# esp32-Prototipo.net
KiCad netlist of a schematic drawn in EAGLE
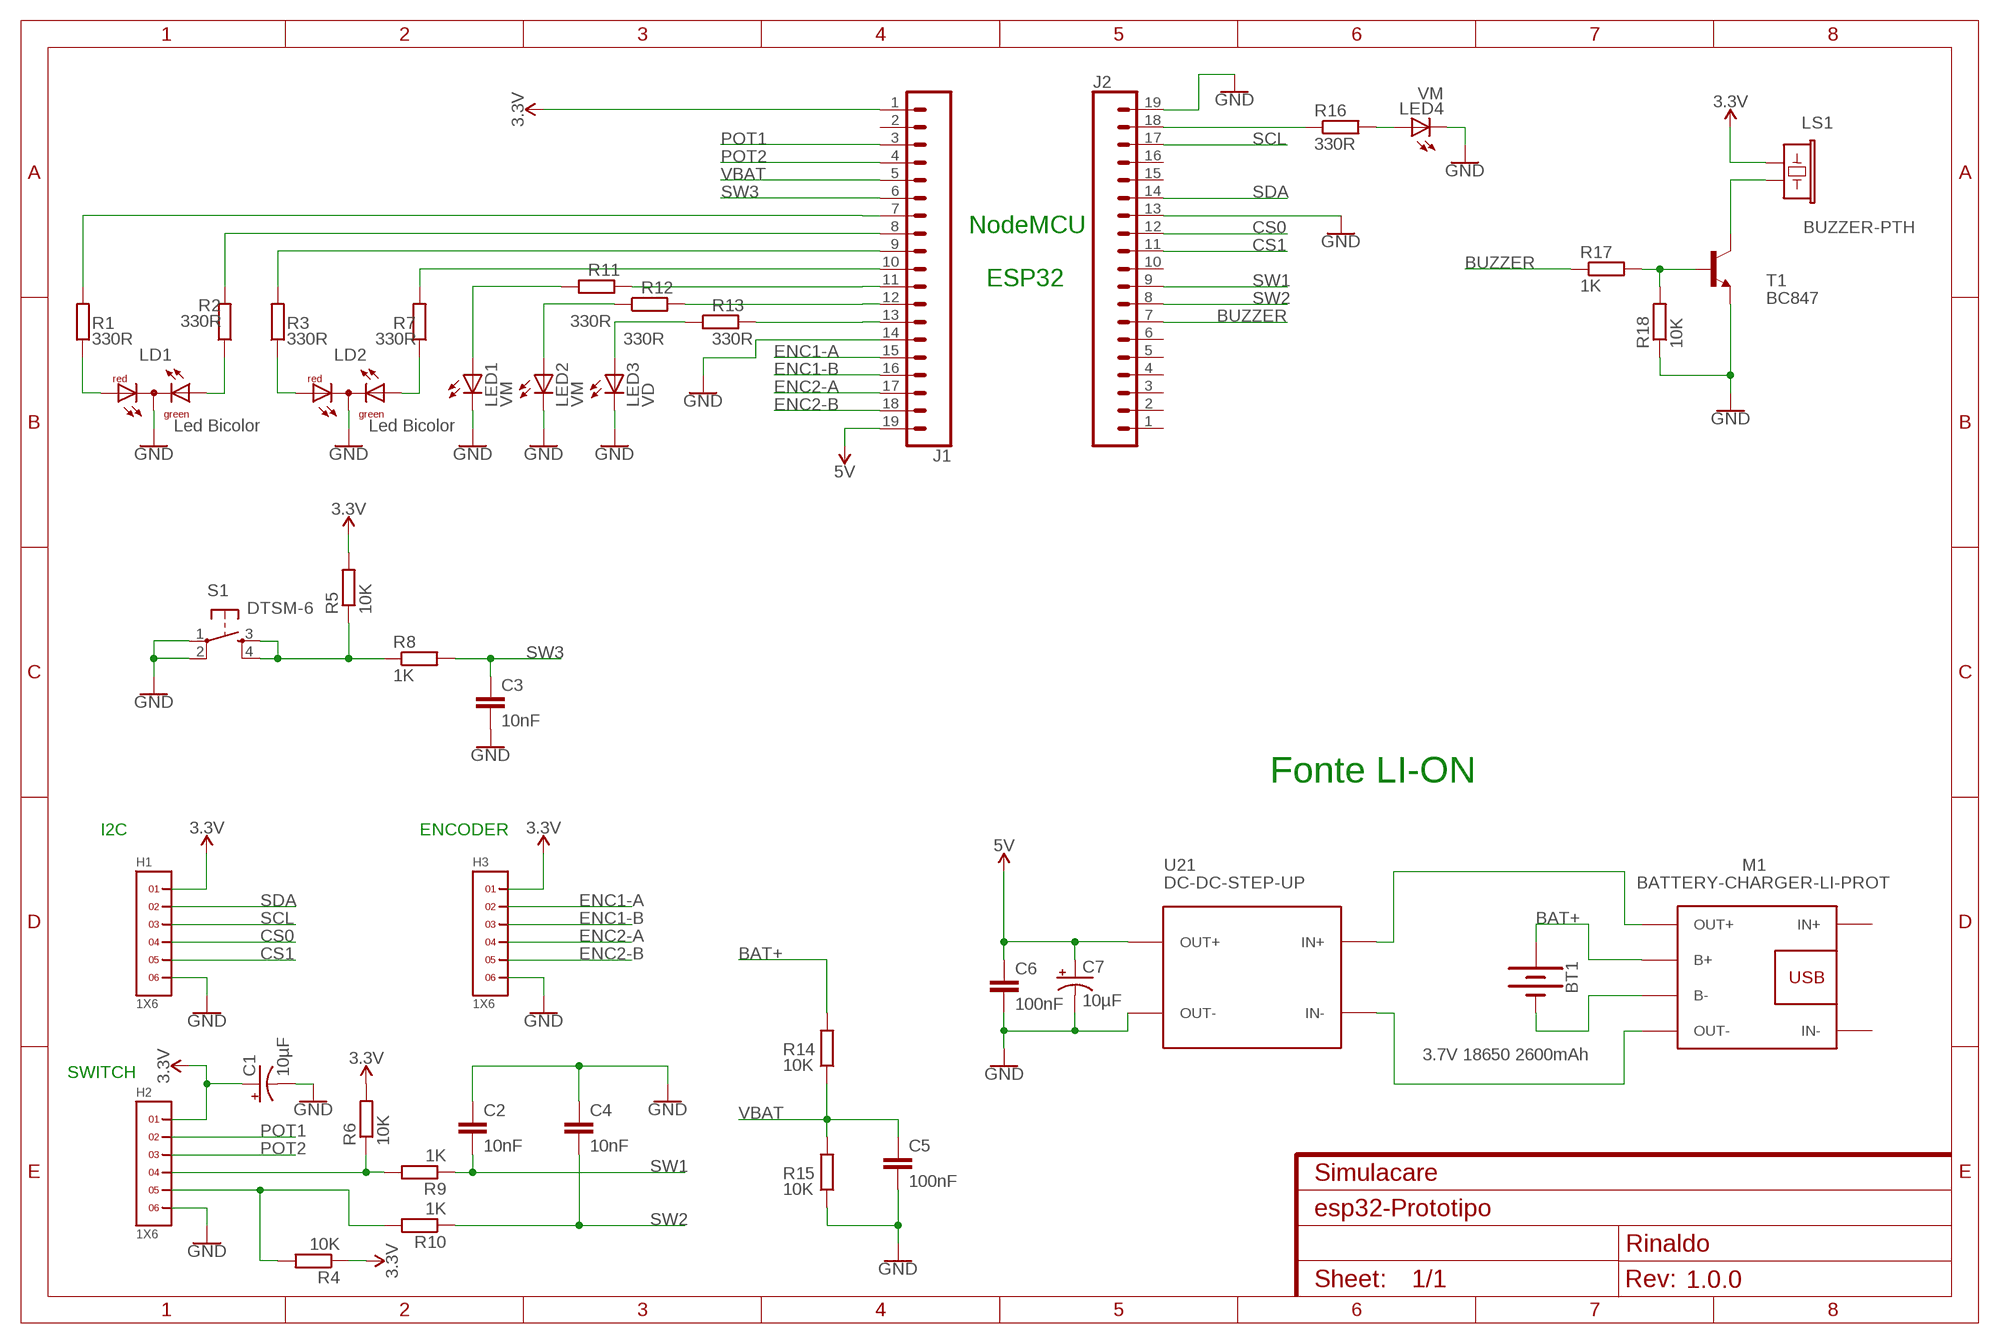
[diagram p0: schematic, sheet 1]

(export (version "E")
  (design (tool "Eeschema 10.0.6"))
  (components
    (comp (ref "BT1")
      (value "3.7V 18650 2600mAh")
      (footprint "eagle-import:BATTERY_18650-HOLDER")
      (libsource (lib "eagle-import") (part "BATTERY-18650"))
    )
    (comp (ref "C1")
      (value "10µF")
      (footprint "eagle-import:EIA6032-NOM")
      (libsource (lib "eagle-import") (part "10UF-POLAR-EIA6032-25V-10%"))
    )
    (comp (ref "C2")
      (value "10nF")
      (footprint "eagle-import:0603")
      (libsource (lib "eagle-import") (part "0.1UF-0603-25V-5%"))
    )
    (comp (ref "C3")
      (value "10nF")
      (footprint "eagle-import:0603")
      (libsource (lib "eagle-import") (part "0.1UF-0603-25V-5%"))
    )
    (comp (ref "C4")
      (value "10nF")
      (footprint "eagle-import:0603")
      (libsource (lib "eagle-import") (part "0.1UF-0603-25V-5%"))
    )
    (comp (ref "C5")
      (value "100nF")
      (footprint "eagle-import:0603")
      (libsource (lib "eagle-import") (part "0.1UF-0603-25V-5%"))
    )
    (comp (ref "C6")
      (value "100nF")
      (footprint "eagle-import:0603")
      (libsource (lib "eagle-import") (part "0.1UF-0603-25V-5%"))
    )
    (comp (ref "C7")
      (value "10µF")
      (footprint "eagle-import:EIA6032-NOM")
      (libsource (lib "eagle-import") (part "10UF-POLAR-EIA6032-25V-10%"))
    )
    (comp (ref "H1")
      (value "1X6")
      (footprint "eagle-import:1X6")
      (libsource (lib "eagle-import") (part "1X6"))
    )
    (comp (ref "H2")
      (value "1X6")
      (footprint "eagle-import:1X6")
      (libsource (lib "eagle-import") (part "1X6"))
    )
    (comp (ref "H3")
      (value "1X6")
      (footprint "eagle-import:1X6")
      (libsource (lib "eagle-import") (part "1X6"))
    )
    (comp (ref "J1")
      (value "CONN_19")
      (footprint "eagle-import:1X19")
      (libsource (lib "eagle-import") (part "CONN_19"))
    )
    (comp (ref "J2")
      (value "CONN_19")
      (footprint "eagle-import:1X19")
      (libsource (lib "eagle-import") (part "CONN_19"))
    )
    (comp (ref "LD1")
      (value "Led Bicolor")
      (footprint "eagle-import:DUOLED-C-5MM")
      (libsource (lib "eagle-import") (part "DUOLED-RG-C"))
    )
    (comp (ref "LD2")
      (value "Led Bicolor")
      (footprint "eagle-import:DUOLED-C-5MM")
      (libsource (lib "eagle-import") (part "DUOLED-RG-C"))
    )
    (comp (ref "LED1")
      (value "VM")
      (footprint "eagle-import:LED5MM")
      (libsource (lib "eagle-import") (part "LED5MM"))
    )
    (comp (ref "LED2")
      (value "VM")
      (footprint "eagle-import:LED5MM")
      (libsource (lib "eagle-import") (part "LED5MM"))
    )
    (comp (ref "LED3")
      (value "VD")
      (footprint "eagle-import:LED5MM")
      (libsource (lib "eagle-import") (part "LED5MM"))
    )
    (comp (ref "LED4")
      (value "VM")
      (footprint "eagle-import:LED5MM")
      (libsource (lib "eagle-import") (part "LED5MM"))
    )
    (comp (ref "LS1")
      (value "BUZZER-PTH")
      (footprint "eagle-import:BUZZER-12MM")
      (libsource (lib "eagle-import") (part "BUZZER-PTH"))
    )
    (comp (ref "M1")
      (value "BATTERY-CHARGER-LI-PROT")
      (footprint "eagle-import:BATTERY-CHARGER-LI-PROT")
      (libsource (lib "eagle-import") (part "BATTERY-CHARGER-LI-PROT"))
    )
    (comp (ref "R1")
      (value "330R")
      (footprint "eagle-import:R0603")
      (libsource (lib "eagle-import") (part "R-EU_R0603"))
    )
    (comp (ref "R2")
      (value "330R")
      (footprint "eagle-import:R0603")
      (libsource (lib "eagle-import") (part "R-EU_R0603"))
    )
    (comp (ref "R3")
      (value "330R")
      (footprint "eagle-import:R0603")
      (libsource (lib "eagle-import") (part "R-EU_R0603"))
    )
    (comp (ref "R4")
      (value "10K")
      (footprint "eagle-import:R0603")
      (libsource (lib "eagle-import") (part "R-EU_R0603"))
    )
    (comp (ref "R5")
      (value "10K")
      (footprint "eagle-import:R0603")
      (libsource (lib "eagle-import") (part "R-EU_R0603"))
    )
    (comp (ref "R6")
      (value "10K")
      (footprint "eagle-import:R0603")
      (libsource (lib "eagle-import") (part "R-EU_R0603"))
    )
    (comp (ref "R7")
      (value "330R")
      (footprint "eagle-import:R0603")
      (libsource (lib "eagle-import") (part "R-EU_R0603"))
    )
    (comp (ref "R8")
      (value "1K")
      (footprint "eagle-import:R0603")
      (libsource (lib "eagle-import") (part "R-EU_R0603"))
    )
    (comp (ref "R9")
      (value "1K")
      (footprint "eagle-import:R0603")
      (libsource (lib "eagle-import") (part "R-EU_R0603"))
    )
    (comp (ref "R10")
      (value "1K")
      (footprint "eagle-import:R0603")
      (libsource (lib "eagle-import") (part "R-EU_R0603"))
    )
    (comp (ref "R11")
      (value "330R")
      (footprint "eagle-import:R0603")
      (libsource (lib "eagle-import") (part "R-EU_R0603"))
    )
    (comp (ref "R12")
      (value "330R")
      (footprint "eagle-import:R0603")
      (libsource (lib "eagle-import") (part "R-EU_R0603"))
    )
    (comp (ref "R13")
      (value "330R")
      (footprint "eagle-import:R0603")
      (libsource (lib "eagle-import") (part "R-EU_R0603"))
    )
    (comp (ref "R14")
      (value "10K")
      (footprint "eagle-import:R0603")
      (libsource (lib "eagle-import") (part "R-EU_R0603"))
    )
    (comp (ref "R15")
      (value "10K")
      (footprint "eagle-import:R0603")
      (libsource (lib "eagle-import") (part "R-EU_R0603"))
    )
    (comp (ref "R16")
      (value "330R")
      (footprint "eagle-import:R0603")
      (libsource (lib "eagle-import") (part "R-EU_R0603"))
    )
    (comp (ref "R17")
      (value "1K")
      (footprint "eagle-import:R0603")
      (libsource (lib "eagle-import") (part "R-EU_R0603"))
    )
    (comp (ref "R18")
      (value "10K")
      (footprint "eagle-import:R0603")
      (libsource (lib "eagle-import") (part "R-EU_R0603"))
    )
    (comp (ref "S1")
      (value "DTSM-6")
      (footprint "eagle-import:DTSM-6")
      (libsource (lib "eagle-import") (part "DTSM-6"))
    )
    (comp (ref "T1")
      (value "BC847")
      (footprint "eagle-import:SOT23")
      (libsource (lib "eagle-import") (part "BC847"))
    )
    (comp (ref "U21")
      (value "DC-DC-STEP-UP")
      (footprint "eagle-import:DC-DC-STEP-UP-MT3608")
      (libsource (lib "eagle-import") (part "DC-DC-STEP-UP-MT3608"))
    )
  )
  (nets
    (net (code "1") (name "/BAT+") (class "Default")
      (node (ref "BT1") (pin "PWR@1") (pinfunction "+_PWR@1") (pintype "power_in"))
      (node (ref "M1") (pin "B+") (pinfunction "B+_B+") (pintype "bidirectional"))
      (node (ref "R14") (pin "2") (pinfunction "2_2") (pintype "passive"))
    )
    (net (code "2") (name "/BUZZER") (class "Default")
      (node (ref "J2") (pin "7") (pinfunction "7_7") (pintype "passive"))
      (node (ref "R17") (pin "1") (pinfunction "1_1") (pintype "passive"))
    )
    (net (code "3") (name "/CS0") (class "Default")
      (node (ref "H1") (pin "4") (pinfunction "4_4") (pintype "bidirectional"))
      (node (ref "J2") (pin "12") (pinfunction "12_12") (pintype "passive"))
    )
    (net (code "4") (name "/CS1") (class "Default")
      (node (ref "H1") (pin "5") (pinfunction "5_5") (pintype "bidirectional"))
      (node (ref "J2") (pin "11") (pinfunction "11_11") (pintype "passive"))
    )
    (net (code "5") (name "/ENC1-A") (class "Default")
      (node (ref "H3") (pin "2") (pinfunction "2_2") (pintype "bidirectional"))
      (node (ref "J1") (pin "15") (pinfunction "15_15") (pintype "passive"))
    )
    (net (code "6") (name "/ENC1-B") (class "Default")
      (node (ref "H3") (pin "3") (pinfunction "3_3") (pintype "bidirectional"))
      (node (ref "J1") (pin "16") (pinfunction "16_16") (pintype "passive"))
    )
    (net (code "7") (name "/ENC2-A") (class "Default")
      (node (ref "H3") (pin "4") (pinfunction "4_4") (pintype "bidirectional"))
      (node (ref "J1") (pin "17") (pinfunction "17_17") (pintype "passive"))
    )
    (net (code "8") (name "/ENC2-B") (class "Default")
      (node (ref "H3") (pin "5") (pinfunction "5_5") (pintype "bidirectional"))
      (node (ref "J1") (pin "18") (pinfunction "18_18") (pintype "passive"))
    )
    (net (code "9") (name "/POT1") (class "Default")
      (node (ref "H2") (pin "2") (pinfunction "2_2") (pintype "bidirectional"))
      (node (ref "J1") (pin "3") (pinfunction "3_3") (pintype "passive"))
    )
    (net (code "10") (name "/POT2") (class "Default")
      (node (ref "H2") (pin "3") (pinfunction "3_3") (pintype "bidirectional"))
      (node (ref "J1") (pin "4") (pinfunction "4_4") (pintype "passive"))
    )
    (net (code "11") (name "/SCL") (class "Default")
      (node (ref "H1") (pin "3") (pinfunction "3_3") (pintype "bidirectional"))
      (node (ref "J2") (pin "17") (pinfunction "17_17") (pintype "passive"))
    )
    (net (code "12") (name "/SDA") (class "Default")
      (node (ref "H1") (pin "2") (pinfunction "2_2") (pintype "bidirectional"))
      (node (ref "J2") (pin "14") (pinfunction "14_14") (pintype "passive"))
    )
    (net (code "13") (name "/SW1") (class "Default")
      (node (ref "C2") (pin "2") (pinfunction "2_2") (pintype "passive"))
      (node (ref "J2") (pin "9") (pinfunction "9_9") (pintype "passive"))
      (node (ref "R9") (pin "1") (pinfunction "1_1") (pintype "passive"))
    )
    (net (code "14") (name "/SW2") (class "Default")
      (node (ref "C4") (pin "2") (pinfunction "2_2") (pintype "passive"))
      (node (ref "J2") (pin "8") (pinfunction "8_8") (pintype "passive"))
      (node (ref "R10") (pin "1") (pinfunction "1_1") (pintype "passive"))
    )
    (net (code "15") (name "/SW3") (class "Default")
      (node (ref "C3") (pin "1") (pinfunction "1_1") (pintype "passive"))
      (node (ref "J1") (pin "6") (pinfunction "6_6") (pintype "passive"))
      (node (ref "R8") (pin "2") (pinfunction "2_2") (pintype "passive"))
    )
    (net (code "16") (name "/VBAT") (class "Default")
      (node (ref "C5") (pin "1") (pinfunction "1_1") (pintype "passive"))
      (node (ref "J1") (pin "5") (pinfunction "5_5") (pintype "passive"))
      (node (ref "R14") (pin "1") (pinfunction "1_1") (pintype "passive"))
      (node (ref "R15") (pin "2") (pinfunction "2_2") (pintype "passive"))
    )
    (net (code "17") (name "3.3V") (class "Default")
      (node (ref "C1") (pin "A") (pinfunction "+_A") (pintype "passive"))
      (node (ref "H1") (pin "1") (pinfunction "1_1") (pintype "bidirectional"))
      (node (ref "H2") (pin "1") (pinfunction "1_1") (pintype "bidirectional"))
      (node (ref "H3") (pin "1") (pinfunction "1_1") (pintype "bidirectional"))
      (node (ref "J1") (pin "1") (pinfunction "1_1") (pintype "passive"))
      (node (ref "LS1") (pin "+") (pinfunction "1_+") (pintype "passive"))
      (node (ref "R4") (pin "1") (pinfunction "1_1") (pintype "passive"))
      (node (ref "R5") (pin "2") (pinfunction "2_2") (pintype "passive"))
      (node (ref "R6") (pin "2") (pinfunction "2_2") (pintype "passive"))
    )
    (net (code "18") (name "5V") (class "Default")
      (node (ref "C6") (pin "1") (pinfunction "1_1") (pintype "passive"))
      (node (ref "C7") (pin "A") (pinfunction "+_A") (pintype "passive"))
      (node (ref "J1") (pin "19") (pinfunction "19_19") (pintype "passive"))
      (node (ref "U21") (pin "OUT+") (pinfunction "OUT+_OUT+") (pintype "bidirectional"))
    )
    (net (code "19") (name "GND") (class "Default")
      (node (ref "C1") (pin "C") (pinfunction "-_C") (pintype "passive"))
      (node (ref "C2") (pin "1") (pinfunction "1_1") (pintype "passive"))
      (node (ref "C3") (pin "2") (pinfunction "2_2") (pintype "passive"))
      (node (ref "C4") (pin "1") (pinfunction "1_1") (pintype "passive"))
      (node (ref "C5") (pin "2") (pinfunction "2_2") (pintype "passive"))
      (node (ref "C6") (pin "2") (pinfunction "2_2") (pintype "passive"))
      (node (ref "C7") (pin "C") (pinfunction "-_C") (pintype "passive"))
      (node (ref "H1") (pin "6") (pinfunction "6_6") (pintype "bidirectional"))
      (node (ref "H2") (pin "6") (pinfunction "6_6") (pintype "bidirectional"))
      (node (ref "H3") (pin "6") (pinfunction "6_6") (pintype "bidirectional"))
      (node (ref "J1") (pin "14") (pinfunction "14_14") (pintype "passive"))
      (node (ref "J2") (pin "13") (pinfunction "13_13") (pintype "passive"))
      (node (ref "J2") (pin "19") (pinfunction "19_19") (pintype "passive"))
      (node (ref "LD1") (pin "C") (pinfunction "C_C") (pintype "passive"))
      (node (ref "LD2") (pin "C") (pinfunction "C_C") (pintype "passive"))
      (node (ref "LED1") (pin "K") (pinfunction "C_K") (pintype "passive"))
      (node (ref "LED2") (pin "K") (pinfunction "C_K") (pintype "passive"))
      (node (ref "LED3") (pin "K") (pinfunction "C_K") (pintype "passive"))
      (node (ref "LED4") (pin "K") (pinfunction "C_K") (pintype "passive"))
      (node (ref "R15") (pin "1") (pinfunction "1_1") (pintype "passive"))
      (node (ref "R18") (pin "1") (pinfunction "1_1") (pintype "passive"))
      (node (ref "S1") (pin "1") (pinfunction "1_1") (pintype "passive"))
      (node (ref "S1") (pin "2") (pinfunction "2_2") (pintype "passive"))
      (node (ref "T1") (pin "2") (pinfunction "E_2") (pintype "passive"))
      (node (ref "U21") (pin "OUT-") (pinfunction "OUT-_OUT-") (pintype "bidirectional"))
    )
    (net (code "20") (name "Net-(BT1--)") (class "Default")
      (node (ref "BT1") (pin "GND@1") (pinfunction "-_GND@1") (pintype "power_in"))
      (node (ref "M1") (pin "B-") (pinfunction "B-_B-") (pintype "bidirectional"))
    )
    (net (code "21") (name "Net-(H2-Pad4)") (class "Default")
      (node (ref "H2") (pin "4") (pinfunction "4_4") (pintype "bidirectional"))
      (node (ref "R6") (pin "1") (pinfunction "1_1") (pintype "passive"))
      (node (ref "R9") (pin "2") (pinfunction "2_2") (pintype "passive"))
    )
    (net (code "22") (name "Net-(H2-Pad5)") (class "Default")
      (node (ref "H2") (pin "5") (pinfunction "5_5") (pintype "bidirectional"))
      (node (ref "R10") (pin "2") (pinfunction "2_2") (pintype "passive"))
      (node (ref "R4") (pin "2") (pinfunction "2_2") (pintype "passive"))
    )
    (net (code "23") (name "Net-(J1-Pad7)") (class "Default")
      (node (ref "J1") (pin "7") (pinfunction "7_7") (pintype "passive"))
      (node (ref "R1") (pin "2") (pinfunction "2_2") (pintype "passive"))
    )
    (net (code "24") (name "Net-(J1-Pad8)") (class "Default")
      (node (ref "J1") (pin "8") (pinfunction "8_8") (pintype "passive"))
      (node (ref "R2") (pin "2") (pinfunction "2_2") (pintype "passive"))
    )
    (net (code "25") (name "Net-(J1-Pad9)") (class "Default")
      (node (ref "J1") (pin "9") (pinfunction "9_9") (pintype "passive"))
      (node (ref "R3") (pin "2") (pinfunction "2_2") (pintype "passive"))
    )
    (net (code "26") (name "Net-(J1-Pad10)") (class "Default")
      (node (ref "J1") (pin "10") (pinfunction "10_10") (pintype "passive"))
      (node (ref "R7") (pin "2") (pinfunction "2_2") (pintype "passive"))
    )
    (net (code "27") (name "Net-(J1-Pad11)") (class "Default")
      (node (ref "J1") (pin "11") (pinfunction "11_11") (pintype "passive"))
      (node (ref "R11") (pin "2") (pinfunction "2_2") (pintype "passive"))
    )
    (net (code "28") (name "Net-(J1-Pad12)") (class "Default")
      (node (ref "J1") (pin "12") (pinfunction "12_12") (pintype "passive"))
      (node (ref "R12") (pin "2") (pinfunction "2_2") (pintype "passive"))
    )
    (net (code "29") (name "Net-(J1-Pad13)") (class "Default")
      (node (ref "J1") (pin "13") (pinfunction "13_13") (pintype "passive"))
      (node (ref "R13") (pin "2") (pinfunction "2_2") (pintype "passive"))
    )
    (net (code "30") (name "Net-(J2-Pad18)") (class "Default")
      (node (ref "J2") (pin "18") (pinfunction "18_18") (pintype "passive"))
      (node (ref "R16") (pin "1") (pinfunction "1_1") (pintype "passive"))
    )
    (net (code "31") (name "Net-(LD1-AG)") (class "Default")
      (node (ref "LD1") (pin "AX") (pinfunction "AG_AX") (pintype "passive"))
      (node (ref "R2") (pin "1") (pinfunction "1_1") (pintype "passive"))
    )
    (net (code "32") (name "Net-(LD1-PadAR)") (class "Default")
      (node (ref "LD1") (pin "AR") (pinfunction "AR_AR") (pintype "passive"))
      (node (ref "R1") (pin "1") (pinfunction "1_1") (pintype "passive"))
    )
    (net (code "33") (name "Net-(LD2-AG)") (class "Default")
      (node (ref "LD2") (pin "AX") (pinfunction "AG_AX") (pintype "passive"))
      (node (ref "R7") (pin "1") (pinfunction "1_1") (pintype "passive"))
    )
    (net (code "34") (name "Net-(LD2-PadAR)") (class "Default")
      (node (ref "LD2") (pin "AR") (pinfunction "AR_AR") (pintype "passive"))
      (node (ref "R3") (pin "1") (pinfunction "1_1") (pintype "passive"))
    )
    (net (code "35") (name "Net-(LED1-PadA)") (class "Default")
      (node (ref "LED1") (pin "A") (pinfunction "A_A") (pintype "passive"))
      (node (ref "R11") (pin "1") (pinfunction "1_1") (pintype "passive"))
    )
    (net (code "36") (name "Net-(LED2-PadA)") (class "Default")
      (node (ref "LED2") (pin "A") (pinfunction "A_A") (pintype "passive"))
      (node (ref "R12") (pin "1") (pinfunction "1_1") (pintype "passive"))
    )
    (net (code "37") (name "Net-(LED3-PadA)") (class "Default")
      (node (ref "LED3") (pin "A") (pinfunction "A_A") (pintype "passive"))
      (node (ref "R13") (pin "1") (pinfunction "1_1") (pintype "passive"))
    )
    (net (code "38") (name "Net-(LED4-PadA)") (class "Default")
      (node (ref "LED4") (pin "A") (pinfunction "A_A") (pintype "passive"))
      (node (ref "R16") (pin "2") (pinfunction "2_2") (pintype "passive"))
    )
    (net (code "39") (name "Net-(LS1-2)") (class "Default")
      (node (ref "LS1") (pin "-") (pinfunction "2_-") (pintype "passive"))
      (node (ref "T1") (pin "3") (pinfunction "C_3") (pintype "passive"))
    )
    (net (code "40") (name "Net-(M1-PadOUT+)") (class "Default")
      (node (ref "M1") (pin "OUT+") (pinfunction "OUT+_OUT+") (pintype "bidirectional"))
      (node (ref "U21") (pin "IN+") (pinfunction "IN+_IN+") (pintype "bidirectional"))
    )
    (net (code "41") (name "Net-(M1-PadOUT-)") (class "Default")
      (node (ref "M1") (pin "OUT-") (pinfunction "OUT-_OUT-") (pintype "bidirectional"))
      (node (ref "U21") (pin "IN-") (pinfunction "IN-_IN-") (pintype "bidirectional"))
    )
    (net (code "42") (name "Net-(R5-Pad1)") (class "Default")
      (node (ref "R5") (pin "1") (pinfunction "1_1") (pintype "passive"))
      (node (ref "R8") (pin "1") (pinfunction "1_1") (pintype "passive"))
      (node (ref "S1") (pin "3") (pinfunction "3_3") (pintype "passive"))
      (node (ref "S1") (pin "4") (pinfunction "4_4") (pintype "passive"))
    )
    (net (code "43") (name "Net-(T1-B)") (class "Default")
      (node (ref "R17") (pin "2") (pinfunction "2_2") (pintype "passive"))
      (node (ref "R18") (pin "2") (pinfunction "2_2") (pintype "passive"))
      (node (ref "T1") (pin "1") (pinfunction "B_1") (pintype "passive"))
    )
    (net (code "44") (name "unconnected-(J1-Pad2)") (class "Default")
      (node (ref "J1") (pin "2") (pinfunction "2_2") (pintype "passive"))
    )
    (net (code "45") (name "unconnected-(J2-Pad1)") (class "Default")
      (node (ref "J2") (pin "1") (pinfunction "1_1") (pintype "passive"))
    )
    (net (code "46") (name "unconnected-(J2-Pad2)") (class "Default")
      (node (ref "J2") (pin "2") (pinfunction "2_2") (pintype "passive"))
    )
    (net (code "47") (name "unconnected-(J2-Pad3)") (class "Default")
      (node (ref "J2") (pin "3") (pinfunction "3_3") (pintype "passive"))
    )
    (net (code "48") (name "unconnected-(J2-Pad4)") (class "Default")
      (node (ref "J2") (pin "4") (pinfunction "4_4") (pintype "passive"))
    )
    (net (code "49") (name "unconnected-(J2-Pad5)") (class "Default")
      (node (ref "J2") (pin "5") (pinfunction "5_5") (pintype "passive"))
    )
    (net (code "50") (name "unconnected-(J2-Pad6)") (class "Default")
      (node (ref "J2") (pin "6") (pinfunction "6_6") (pintype "passive"))
    )
    (net (code "51") (name "unconnected-(J2-Pad10)") (class "Default")
      (node (ref "J2") (pin "10") (pinfunction "10_10") (pintype "passive"))
    )
    (net (code "52") (name "unconnected-(J2-Pad15)") (class "Default")
      (node (ref "J2") (pin "15") (pinfunction "15_15") (pintype "passive"))
    )
    (net (code "53") (name "unconnected-(J2-Pad16)") (class "Default")
      (node (ref "J2") (pin "16") (pinfunction "16_16") (pintype "passive"))
    )
    (net (code "54") (name "unconnected-(M1-PadIN+)") (class "Default")
      (node (ref "M1") (pin "IN+") (pinfunction "IN+_IN+") (pintype "bidirectional"))
    )
    (net (code "55") (name "unconnected-(M1-PadIN-)") (class "Default")
      (node (ref "M1") (pin "IN-") (pinfunction "IN-_IN-") (pintype "bidirectional"))
    )
  )
)
